# 780-00055_rev1_Pg4_SCH_NRES_Temp_Meas_8-.net
KiCad netlist of a schematic drawn in Altium Designer
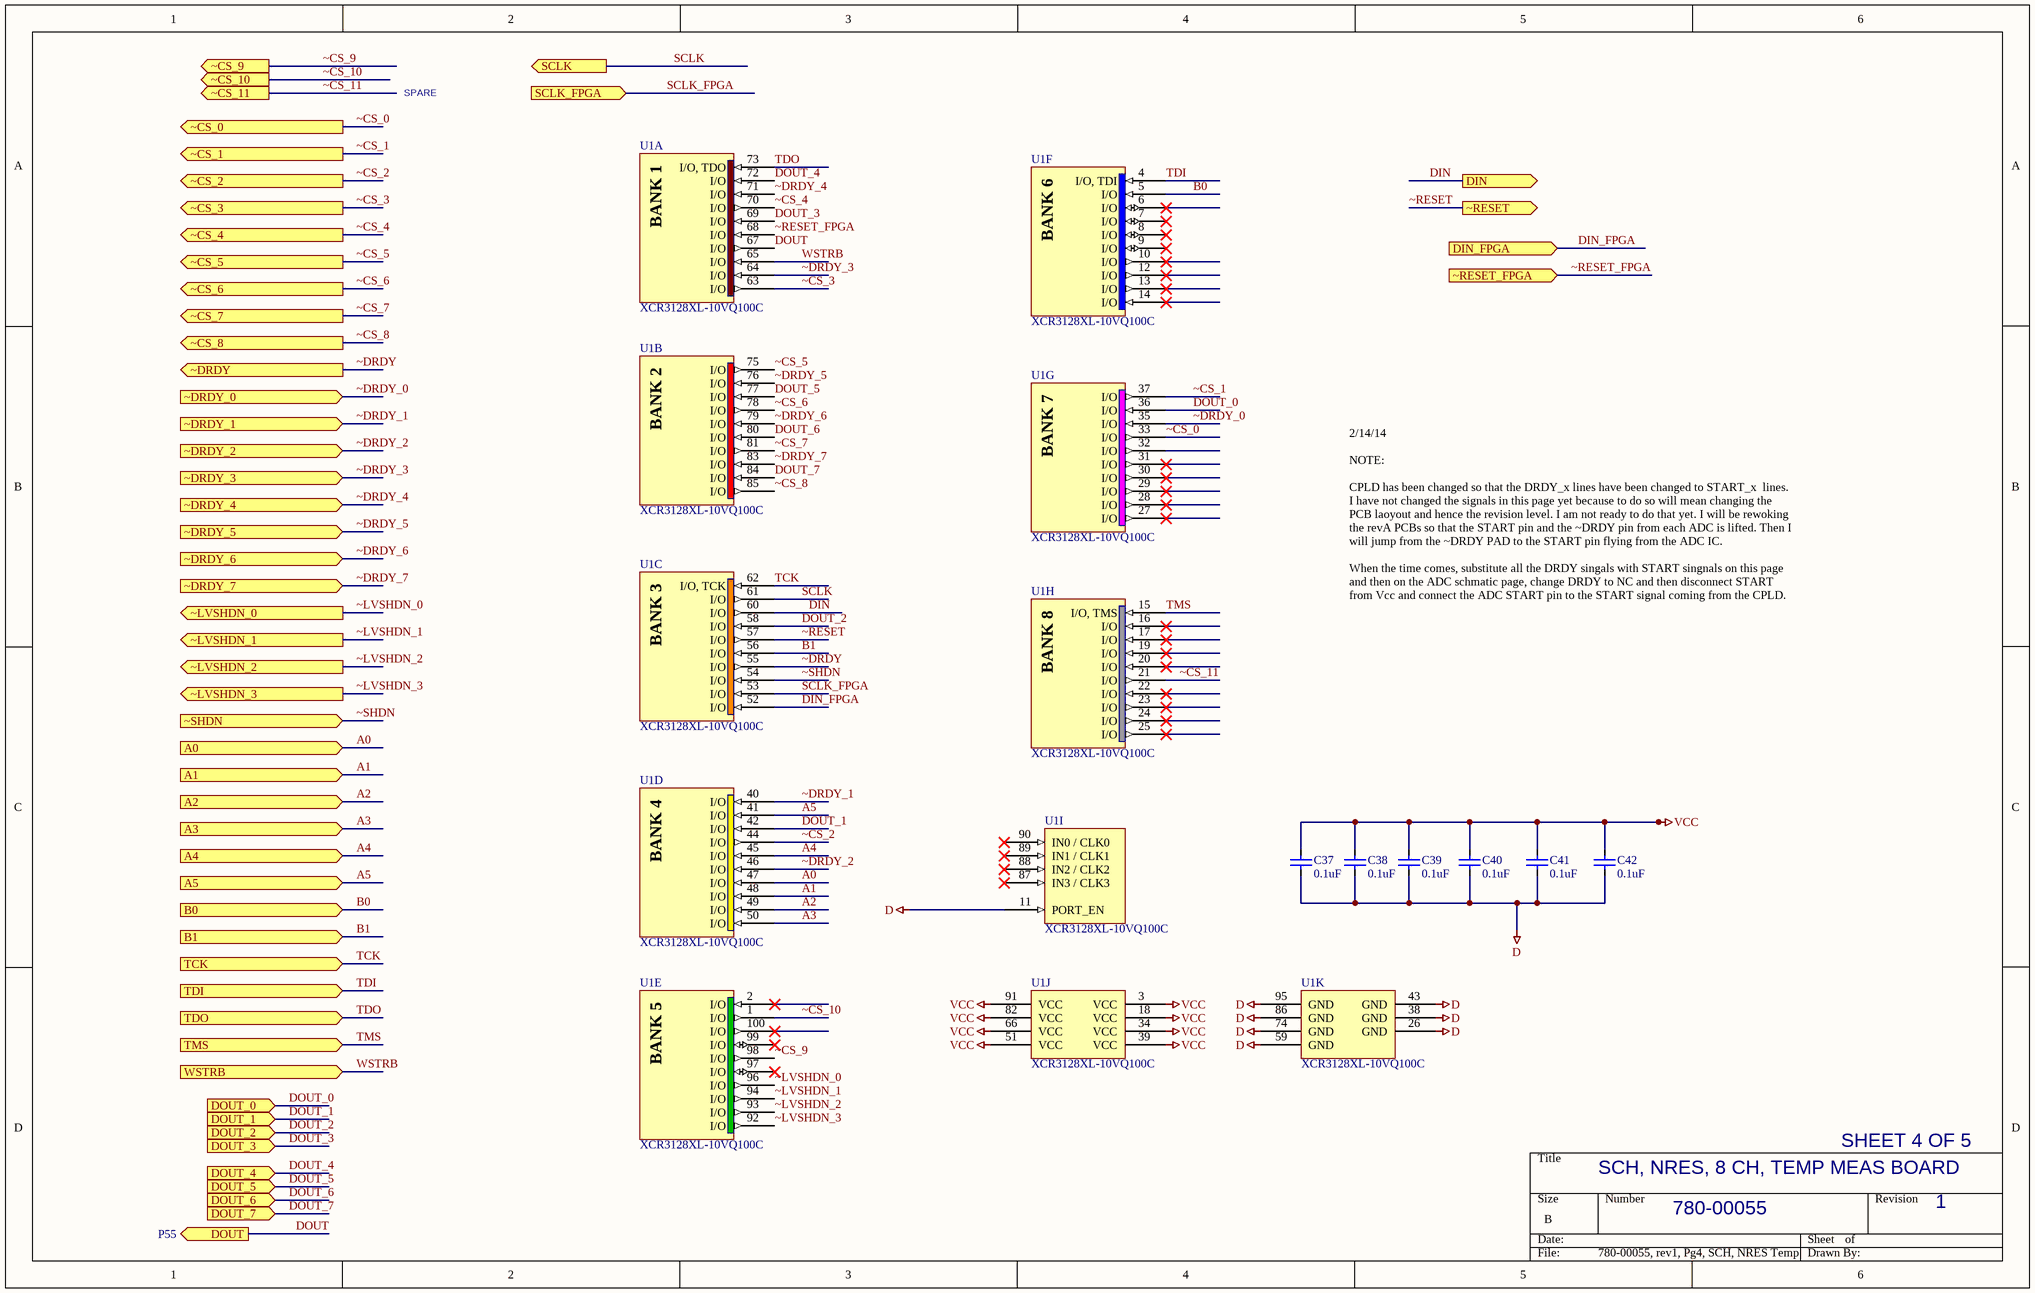
[diagram p0: 780-00055, rev1, Pg4, SCH, NRES Temp Meas, 8-Chan RTD .SchDoc]

(export (version "E")
  (design (tool "Eeschema 10.0.6"))
  (components
    (comp (ref "C37")
      (value "0.1uF")
      (footprint "SMD_0805")
      (description "Capacitor")
      (fields (field (name "MANUFACTURER") "AVX") (field (name "Comment") "Cap SMD"))
      (libsource (lib "Richs Schematic Components") (part "Cap SMD"))
    )
    (comp (ref "C38")
      (value "0.1uF")
      (footprint "SMD_0805")
      (description "Capacitor")
      (fields (field (name "MANUFACTURER") "AVX") (field (name "Comment") "Cap SMD"))
      (libsource (lib "Richs Schematic Components") (part "Cap SMD"))
    )
    (comp (ref "C39")
      (value "0.1uF")
      (footprint "SMD_0805")
      (description "Capacitor")
      (fields (field (name "MANUFACTURER") "AVX") (field (name "Comment") "Cap SMD"))
      (libsource (lib "Richs Schematic Components") (part "Cap SMD"))
    )
    (comp (ref "C40")
      (value "0.1uF")
      (footprint "SMD_0805")
      (description "Capacitor")
      (fields (field (name "MANUFACTURER") "AVX") (field (name "Comment") "Cap SMD"))
      (libsource (lib "Richs Schematic Components") (part "Cap SMD"))
    )
    (comp (ref "C41")
      (value "0.1uF")
      (footprint "SMD_0805")
      (description "Capacitor")
      (fields (field (name "MANUFACTURER") "AVX") (field (name "Comment") "Cap SMD"))
      (libsource (lib "Richs Schematic Components") (part "Cap SMD"))
    )
    (comp (ref "C42")
      (value "0.1uF")
      (footprint "SMD_0805")
      (description "Capacitor")
      (fields (field (name "MANUFACTURER") "AVX") (field (name "Comment") "Cap SMD"))
      (libsource (lib "Richs Schematic Components") (part "Cap SMD"))
    )
    (comp (ref "U1")
      (value "XCR3128XL-10VQ100C")
      (footprint "VQ100_N")
      (description "CoolRunner XPLA3 3.3V, 128 Macrocell CPLD, 84 User I/Os, 100-Pin VQFP, Commercial Grade")
      (libsource (lib "Xilinx CoolRunner XPLA3") (part "XCR3128XL-10VQ100C"))
    )
  )
  (nets
    (net (code "1") (name "/A0") (class "Default")
      (node (ref "U1") (pin "47") (pinfunction "I/O_47") (pintype "input"))
    )
    (net (code "2") (name "/A1") (class "Default")
      (node (ref "U1") (pin "48") (pinfunction "I/O_48") (pintype "input"))
    )
    (net (code "3") (name "/A2") (class "Default")
      (node (ref "U1") (pin "49") (pinfunction "I/O_49") (pintype "input"))
    )
    (net (code "4") (name "/A3") (class "Default")
      (node (ref "U1") (pin "50") (pinfunction "I/O_50") (pintype "input"))
    )
    (net (code "5") (name "/A4") (class "Default")
      (node (ref "U1") (pin "45") (pinfunction "I/O_45") (pintype "input"))
    )
    (net (code "6") (name "/A5") (class "Default")
      (node (ref "U1") (pin "41") (pinfunction "I/O_41") (pintype "input"))
    )
    (net (code "7") (name "/B0") (class "Default")
      (node (ref "U1") (pin "5") (pinfunction "I/O_5") (pintype "input"))
    )
    (net (code "8") (name "/B1") (class "Default")
      (node (ref "U1") (pin "56") (pinfunction "I/O_56") (pintype "input"))
    )
    (net (code "9") (name "/DIN") (class "Default")
      (node (ref "U1") (pin "60") (pinfunction "I/O_60") (pintype "output"))
    )
    (net (code "10") (name "/DIN_FPGA") (class "Default")
      (node (ref "U1") (pin "52") (pinfunction "I/O_52") (pintype "input"))
    )
    (net (code "11") (name "/DOUT") (class "Default")
      (node (ref "U1") (pin "67") (pinfunction "I/O_67") (pintype "output"))
    )
    (net (code "12") (name "/DOUT_0") (class "Default")
      (node (ref "U1") (pin "36") (pinfunction "I/O_36") (pintype "input"))
    )
    (net (code "13") (name "/DOUT_1") (class "Default")
      (node (ref "U1") (pin "42") (pinfunction "I/O_42") (pintype "input"))
    )
    (net (code "14") (name "/DOUT_2") (class "Default")
      (node (ref "U1") (pin "58") (pinfunction "I/O_58") (pintype "input"))
    )
    (net (code "15") (name "/DOUT_3") (class "Default")
      (node (ref "U1") (pin "69") (pinfunction "I/O_69") (pintype "input"))
    )
    (net (code "16") (name "/DOUT_4") (class "Default")
      (node (ref "U1") (pin "72") (pinfunction "I/O_72") (pintype "input"))
    )
    (net (code "17") (name "/DOUT_5") (class "Default")
      (node (ref "U1") (pin "77") (pinfunction "I/O_77") (pintype "input"))
    )
    (net (code "18") (name "/DOUT_6") (class "Default")
      (node (ref "U1") (pin "80") (pinfunction "I/O_80") (pintype "input"))
    )
    (net (code "19") (name "/DOUT_7") (class "Default")
      (node (ref "U1") (pin "84") (pinfunction "I/O_84") (pintype "input"))
    )
    (net (code "20") (name "/SCLK") (class "Default")
      (node (ref "U1") (pin "61") (pinfunction "I/O_61") (pintype "output"))
    )
    (net (code "21") (name "/SCLK_FPGA") (class "Default")
      (node (ref "U1") (pin "53") (pinfunction "I/O_53") (pintype "input"))
    )
    (net (code "22") (name "/TCK") (class "Default")
      (node (ref "U1") (pin "62") (pinfunction "I/O,_TCK_62") (pintype "input"))
    )
    (net (code "23") (name "/TDI") (class "Default")
      (node (ref "U1") (pin "4") (pinfunction "I/O,_TDI_4") (pintype "input"))
    )
    (net (code "24") (name "/TDO") (class "Default")
      (node (ref "U1") (pin "73") (pinfunction "I/O,_TDO_73") (pintype "input"))
    )
    (net (code "25") (name "/TMS") (class "Default")
      (node (ref "U1") (pin "15") (pinfunction "I/O,_TMS_15") (pintype "input"))
    )
    (net (code "26") (name "/WSTRB") (class "Default")
      (node (ref "U1") (pin "65") (pinfunction "I/O_65") (pintype "input"))
    )
    (net (code "27") (name "/~CS_0") (class "Default")
      (node (ref "U1") (pin "33") (pinfunction "I/O_33") (pintype "output"))
    )
    (net (code "28") (name "/~CS_1") (class "Default")
      (node (ref "U1") (pin "37") (pinfunction "I/O_37") (pintype "output"))
    )
    (net (code "29") (name "/~CS_2") (class "Default")
      (node (ref "U1") (pin "44") (pinfunction "I/O_44") (pintype "output"))
    )
    (net (code "30") (name "/~CS_3") (class "Default")
      (node (ref "U1") (pin "63") (pinfunction "I/O_63") (pintype "output"))
    )
    (net (code "31") (name "/~CS_4") (class "Default")
      (node (ref "U1") (pin "70") (pinfunction "I/O_70") (pintype "output"))
    )
    (net (code "32") (name "/~CS_5") (class "Default")
      (node (ref "U1") (pin "75") (pinfunction "I/O_75") (pintype "output"))
    )
    (net (code "33") (name "/~CS_6") (class "Default")
      (node (ref "U1") (pin "78") (pinfunction "I/O_78") (pintype "output"))
    )
    (net (code "34") (name "/~CS_7") (class "Default")
      (node (ref "U1") (pin "81") (pinfunction "I/O_81") (pintype "output"))
    )
    (net (code "35") (name "/~CS_8") (class "Default")
      (node (ref "U1") (pin "85") (pinfunction "I/O_85") (pintype "output"))
    )
    (net (code "36") (name "/~CS_9") (class "Default")
      (node (ref "U1") (pin "98") (pinfunction "I/O_98") (pintype "output"))
    )
    (net (code "37") (name "/~CS_10") (class "Default")
      (node (ref "U1") (pin "1") (pinfunction "I/O_1") (pintype "output"))
    )
    (net (code "38") (name "/~CS_11") (class "Default")
      (node (ref "U1") (pin "21") (pinfunction "I/O_21") (pintype "output"))
    )
    (net (code "39") (name "/~DRDY") (class "Default")
      (node (ref "U1") (pin "55") (pinfunction "I/O_55") (pintype "output"))
    )
    (net (code "40") (name "/~DRDY_0") (class "Default")
      (node (ref "U1") (pin "35") (pinfunction "I/O_35") (pintype "input"))
    )
    (net (code "41") (name "/~DRDY_1") (class "Default")
      (node (ref "U1") (pin "40") (pinfunction "I/O_40") (pintype "input"))
    )
    (net (code "42") (name "/~DRDY_2") (class "Default")
      (node (ref "U1") (pin "46") (pinfunction "I/O_46") (pintype "input"))
    )
    (net (code "43") (name "/~DRDY_3") (class "Default")
      (node (ref "U1") (pin "64") (pinfunction "I/O_64") (pintype "input"))
    )
    (net (code "44") (name "/~DRDY_4") (class "Default")
      (node (ref "U1") (pin "71") (pinfunction "I/O_71") (pintype "input"))
    )
    (net (code "45") (name "/~DRDY_5") (class "Default")
      (node (ref "U1") (pin "76") (pinfunction "I/O_76") (pintype "input"))
    )
    (net (code "46") (name "/~DRDY_6") (class "Default")
      (node (ref "U1") (pin "79") (pinfunction "I/O_79") (pintype "input"))
    )
    (net (code "47") (name "/~DRDY_7") (class "Default")
      (node (ref "U1") (pin "83") (pinfunction "I/O_83") (pintype "input"))
    )
    (net (code "48") (name "/~LVSHDN_0") (class "Default")
      (node (ref "U1") (pin "96") (pinfunction "I/O_96") (pintype "output"))
    )
    (net (code "49") (name "/~LVSHDN_1") (class "Default")
      (node (ref "U1") (pin "94") (pinfunction "I/O_94") (pintype "output"))
    )
    (net (code "50") (name "/~LVSHDN_2") (class "Default")
      (node (ref "U1") (pin "93") (pinfunction "I/O_93") (pintype "output"))
    )
    (net (code "51") (name "/~LVSHDN_3") (class "Default")
      (node (ref "U1") (pin "92") (pinfunction "I/O_92") (pintype "output"))
    )
    (net (code "52") (name "/~RESET") (class "Default")
      (node (ref "U1") (pin "57") (pinfunction "I/O_57") (pintype "output"))
    )
    (net (code "53") (name "/~RESET_FPGA") (class "Default")
      (node (ref "U1") (pin "68") (pinfunction "I/O_68") (pintype "input"))
    )
    (net (code "54") (name "/~SHDN") (class "Default")
      (node (ref "U1") (pin "54") (pinfunction "I/O_54") (pintype "input"))
    )
    (net (code "55") (name "D") (class "Default")
      (node (ref "C37") (pin "1") (pinfunction "1_1") (pintype "passive"))
      (node (ref "C38") (pin "1") (pinfunction "1_1") (pintype "passive"))
      (node (ref "C39") (pin "1") (pinfunction "1_1") (pintype "passive"))
      (node (ref "C40") (pin "1") (pinfunction "1_1") (pintype "passive"))
      (node (ref "C41") (pin "1") (pinfunction "1_1") (pintype "passive"))
      (node (ref "C42") (pin "1") (pinfunction "1_1") (pintype "passive"))
      (node (ref "U1") (pin "11") (pinfunction "PORT_EN_11") (pintype "input"))
      (node (ref "U1") (pin "26") (pinfunction "GND_26") (pintype "power_in"))
      (node (ref "U1") (pin "38") (pinfunction "GND_38") (pintype "power_in"))
      (node (ref "U1") (pin "43") (pinfunction "GND_43") (pintype "power_in"))
      (node (ref "U1") (pin "59") (pinfunction "GND_59") (pintype "power_in"))
      (node (ref "U1") (pin "74") (pinfunction "GND_74") (pintype "power_in"))
      (node (ref "U1") (pin "86") (pinfunction "GND_86") (pintype "power_in"))
      (node (ref "U1") (pin "95") (pinfunction "GND_95") (pintype "power_in"))
    )
    (net (code "56") (name "VCC") (class "Default")
      (node (ref "C37") (pin "2") (pinfunction "2_2") (pintype "passive"))
      (node (ref "C38") (pin "2") (pinfunction "2_2") (pintype "passive"))
      (node (ref "C39") (pin "2") (pinfunction "2_2") (pintype "passive"))
      (node (ref "C40") (pin "2") (pinfunction "2_2") (pintype "passive"))
      (node (ref "C41") (pin "2") (pinfunction "2_2") (pintype "passive"))
      (node (ref "C42") (pin "2") (pinfunction "2_2") (pintype "passive"))
      (node (ref "U1") (pin "18") (pinfunction "VCC_18") (pintype "power_in"))
      (node (ref "U1") (pin "3") (pinfunction "VCC_3") (pintype "power_in"))
      (node (ref "U1") (pin "34") (pinfunction "VCC_34") (pintype "power_in"))
      (node (ref "U1") (pin "39") (pinfunction "VCC_39") (pintype "power_in"))
      (node (ref "U1") (pin "51") (pinfunction "VCC_51") (pintype "power_in"))
      (node (ref "U1") (pin "66") (pinfunction "VCC_66") (pintype "power_in"))
      (node (ref "U1") (pin "82") (pinfunction "VCC_82") (pintype "power_in"))
      (node (ref "U1") (pin "91") (pinfunction "VCC_91") (pintype "power_in"))
    )
    (net (code "57") (name "unconnected-(U1E-I{slash}O-Pad2)") (class "Default")
      (node (ref "U1") (pin "2") (pinfunction "I/O_2") (pintype "input+no_connect"))
    )
    (net (code "58") (name "unconnected-(U1E-I{slash}O-Pad97)") (class "Default")
      (node (ref "U1") (pin "97") (pinfunction "I/O_97") (pintype "bidirectional+no_connect"))
    )
    (net (code "59") (name "unconnected-(U1E-I{slash}O-Pad99)") (class "Default")
      (node (ref "U1") (pin "99") (pinfunction "I/O_99") (pintype "bidirectional+no_connect"))
    )
    (net (code "60") (name "unconnected-(U1E-I{slash}O-Pad100)") (class "Default")
      (node (ref "U1") (pin "100") (pinfunction "I/O_100") (pintype "output+no_connect"))
    )
    (net (code "61") (name "unconnected-(U1F-I{slash}O-Pad6)") (class "Default")
      (node (ref "U1") (pin "6") (pinfunction "I/O_6") (pintype "bidirectional+no_connect"))
    )
    (net (code "62") (name "unconnected-(U1F-I{slash}O-Pad7)") (class "Default")
      (node (ref "U1") (pin "7") (pinfunction "I/O_7") (pintype "bidirectional+no_connect"))
    )
    (net (code "63") (name "unconnected-(U1F-I{slash}O-Pad8)") (class "Default")
      (node (ref "U1") (pin "8") (pinfunction "I/O_8") (pintype "bidirectional+no_connect"))
    )
    (net (code "64") (name "unconnected-(U1F-I{slash}O-Pad9)") (class "Default")
      (node (ref "U1") (pin "9") (pinfunction "I/O_9") (pintype "bidirectional+no_connect"))
    )
    (net (code "65") (name "unconnected-(U1F-I{slash}O-Pad10)") (class "Default")
      (node (ref "U1") (pin "10") (pinfunction "I/O_10") (pintype "output+no_connect"))
    )
    (net (code "66") (name "unconnected-(U1F-I{slash}O-Pad12)") (class "Default")
      (node (ref "U1") (pin "12") (pinfunction "I/O_12") (pintype "output+no_connect"))
    )
    (net (code "67") (name "unconnected-(U1F-I{slash}O-Pad13)") (class "Default")
      (node (ref "U1") (pin "13") (pinfunction "I/O_13") (pintype "output+no_connect"))
    )
    (net (code "68") (name "unconnected-(U1F-I{slash}O-Pad14)") (class "Default")
      (node (ref "U1") (pin "14") (pinfunction "I/O_14") (pintype "input+no_connect"))
    )
    (net (code "69") (name "unconnected-(U1G-I{slash}O-Pad27)") (class "Default")
      (node (ref "U1") (pin "27") (pinfunction "I/O_27") (pintype "output+no_connect"))
    )
    (net (code "70") (name "unconnected-(U1G-I{slash}O-Pad28)") (class "Default")
      (node (ref "U1") (pin "28") (pinfunction "I/O_28") (pintype "output+no_connect"))
    )
    (net (code "71") (name "unconnected-(U1G-I{slash}O-Pad29)") (class "Default")
      (node (ref "U1") (pin "29") (pinfunction "I/O_29") (pintype "output+no_connect"))
    )
    (net (code "72") (name "unconnected-(U1G-I{slash}O-Pad30)") (class "Default")
      (node (ref "U1") (pin "30") (pinfunction "I/O_30") (pintype "output+no_connect"))
    )
    (net (code "73") (name "unconnected-(U1G-I{slash}O-Pad31)") (class "Default")
      (node (ref "U1") (pin "31") (pinfunction "I/O_31") (pintype "output+no_connect"))
    )
    (net (code "74") (name "unconnected-(U1G-I{slash}O-Pad32)") (class "Default")
      (node (ref "U1") (pin "32") (pinfunction "I/O_32") (pintype "output"))
    )
    (net (code "75") (name "unconnected-(U1H-I{slash}O-Pad16)") (class "Default")
      (node (ref "U1") (pin "16") (pinfunction "I/O_16") (pintype "input+no_connect"))
    )
    (net (code "76") (name "unconnected-(U1H-I{slash}O-Pad17)") (class "Default")
      (node (ref "U1") (pin "17") (pinfunction "I/O_17") (pintype "input+no_connect"))
    )
    (net (code "77") (name "unconnected-(U1H-I{slash}O-Pad19)") (class "Default")
      (node (ref "U1") (pin "19") (pinfunction "I/O_19") (pintype "input+no_connect"))
    )
    (net (code "78") (name "unconnected-(U1H-I{slash}O-Pad20)") (class "Default")
      (node (ref "U1") (pin "20") (pinfunction "I/O_20") (pintype "input+no_connect"))
    )
    (net (code "79") (name "unconnected-(U1H-I{slash}O-Pad22)") (class "Default")
      (node (ref "U1") (pin "22") (pinfunction "I/O_22") (pintype "input+no_connect"))
    )
    (net (code "80") (name "unconnected-(U1H-I{slash}O-Pad23)") (class "Default")
      (node (ref "U1") (pin "23") (pinfunction "I/O_23") (pintype "output+no_connect"))
    )
    (net (code "81") (name "unconnected-(U1H-I{slash}O-Pad24)") (class "Default")
      (node (ref "U1") (pin "24") (pinfunction "I/O_24") (pintype "output+no_connect"))
    )
    (net (code "82") (name "unconnected-(U1H-I{slash}O-Pad25)") (class "Default")
      (node (ref "U1") (pin "25") (pinfunction "I/O_25") (pintype "output+no_connect"))
    )
    (net (code "83") (name "unconnected-(U1I-IN0_{slash}_CLK0-Pad90)") (class "Default")
      (node (ref "U1") (pin "90") (pinfunction "IN0_/_CLK0_90") (pintype "input+no_connect"))
    )
    (net (code "84") (name "unconnected-(U1I-IN1_{slash}_CLK1-Pad89)") (class "Default")
      (node (ref "U1") (pin "89") (pinfunction "IN1_/_CLK1_89") (pintype "input+no_connect"))
    )
    (net (code "85") (name "unconnected-(U1I-IN2_{slash}_CLK2-Pad88)") (class "Default")
      (node (ref "U1") (pin "88") (pinfunction "IN2_/_CLK2_88") (pintype "input+no_connect"))
    )
    (net (code "86") (name "unconnected-(U1I-IN3_{slash}_CLK3-Pad87)") (class "Default")
      (node (ref "U1") (pin "87") (pinfunction "IN3_/_CLK3_87") (pintype "input+no_connect"))
    )
  )
)
